# AUDIO.net
KiCad netlist of a schematic drawn in Altium Designer
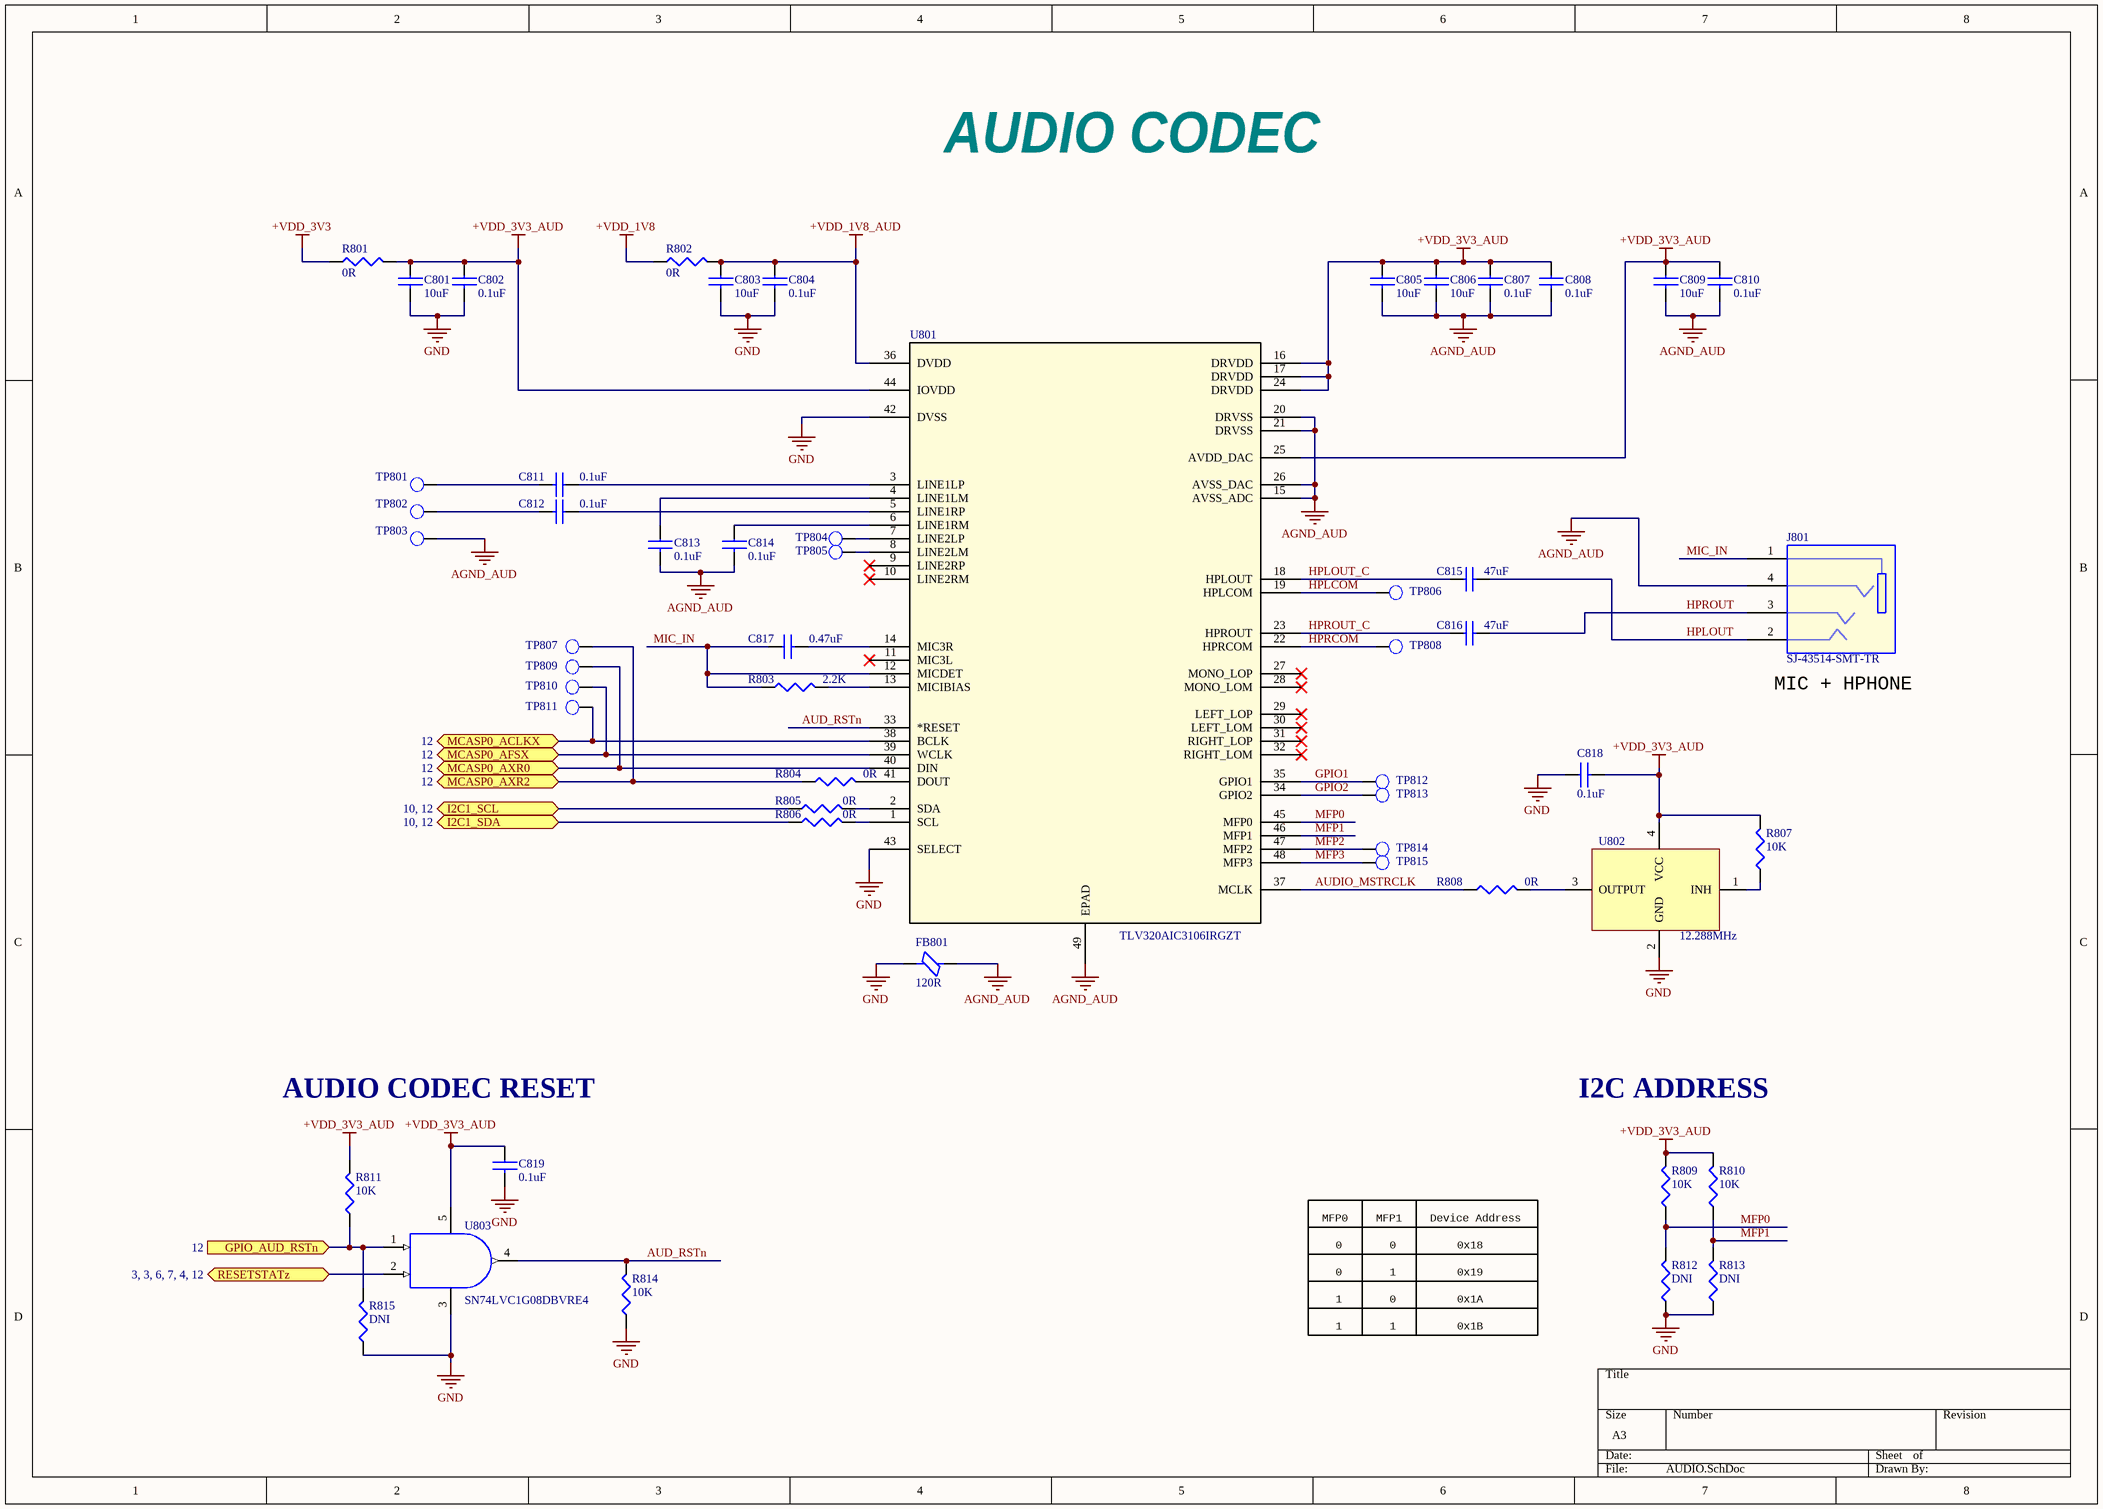
[diagram p0: AUDIO.SchDoc]

(export (version "E")
  (design (tool "Eeschema 10.0.6"))
  (components
    (comp (ref "C801")
      (value "10uF")
      (footprint "C0402")
      (description "Multilayer Ceramic Capacitor, 10 uF, 10 V, ± 20%, X5R, 0402 [1005 Metric]")
      (fields
        (field (name "MANUFACTURER") "Murata")
        (field (name "MANUFACTURER PART NUMBER") "GRM155R61A106ME11D")
      )
      (libsource (lib "Schlib SOM AM625") (part "GRM155R61A106ME11D"))
    )
    (comp (ref "C802")
      (value "0.1uF")
      (footprint "C0201")
      (description "Multilayer Ceramic Capacitor, 0.1 uF, 16 V, ± 10%, X5R, 0201 [0603 Metric]")
      (fields
        (field (name "MANUFACTURER") "Murata")
        (field (name "MANUFACTURER PART NUMBER") "GRM033R61C104KE14D")
      )
      (libsource (lib "Schlib SOM AM625") (part "GRM033R61C104KE14D"))
    )
    (comp (ref "C803")
      (value "10uF")
      (footprint "C0402")
      (description "Multilayer Ceramic Capacitor, 10 uF, 10 V, ± 20%, X5R, 0402 [1005 Metric]")
      (fields
        (field (name "MANUFACTURER") "Murata")
        (field (name "MANUFACTURER PART NUMBER") "GRM155R61A106ME11D")
      )
      (libsource (lib "Schlib SOM AM625") (part "GRM155R61A106ME11D"))
    )
    (comp (ref "C804")
      (value "0.1uF")
      (footprint "C0201")
      (description "Multilayer Ceramic Capacitor, 0.1 uF, 16 V, ± 10%, X5R, 0201 [0603 Metric]")
      (fields
        (field (name "MANUFACTURER") "Murata")
        (field (name "MANUFACTURER PART NUMBER") "GRM033R61C104KE14D")
      )
      (libsource (lib "Schlib SOM AM625") (part "GRM033R61C104KE14D"))
    )
    (comp (ref "C805")
      (value "10uF")
      (footprint "C0402")
      (description "Multilayer Ceramic Capacitor, 10 uF, 10 V, ± 20%, X5R, 0402 [1005 Metric]")
      (fields
        (field (name "MANUFACTURER") "Murata")
        (field (name "MANUFACTURER PART NUMBER") "GRM155R61A106ME11D")
      )
      (libsource (lib "Schlib SOM AM625") (part "GRM155R61A106ME11D"))
    )
    (comp (ref "C806")
      (value "10uF")
      (footprint "C0402")
      (description "Multilayer Ceramic Capacitor, 10 uF, 10 V, ± 20%, X5R, 0402 [1005 Metric]")
      (fields
        (field (name "MANUFACTURER") "Murata")
        (field (name "MANUFACTURER PART NUMBER") "GRM155R61A106ME11D")
      )
      (libsource (lib "Schlib SOM AM625") (part "GRM155R61A106ME11D"))
    )
    (comp (ref "C807")
      (value "0.1uF")
      (footprint "C0201")
      (description "Multilayer Ceramic Capacitor, 0.1 uF, 16 V, ± 10%, X5R, 0201 [0603 Metric]")
      (fields
        (field (name "MANUFACTURER") "Murata")
        (field (name "MANUFACTURER PART NUMBER") "GRM033R61C104KE14D")
      )
      (libsource (lib "Schlib SOM AM625") (part "GRM033R61C104KE14D"))
    )
    (comp (ref "C808")
      (value "0.1uF")
      (footprint "C0201")
      (description "Multilayer Ceramic Capacitor, 0.1 uF, 16 V, ± 10%, X5R, 0201 [0603 Metric]")
      (fields
        (field (name "MANUFACTURER") "Murata")
        (field (name "MANUFACTURER PART NUMBER") "GRM033R61C104KE14D")
      )
      (libsource (lib "Schlib SOM AM625") (part "GRM033R61C104KE14D"))
    )
    (comp (ref "C809")
      (value "10uF")
      (footprint "C0402")
      (description "Multilayer Ceramic Capacitor, 10 uF, 10 V, ± 20%, X5R, 0402 [1005 Metric]")
      (fields
        (field (name "MANUFACTURER") "Murata")
        (field (name "MANUFACTURER PART NUMBER") "GRM155R61A106ME11D")
      )
      (libsource (lib "Schlib SOM AM625") (part "GRM155R61A106ME11D"))
    )
    (comp (ref "C810")
      (value "0.1uF")
      (footprint "C0201")
      (description "Multilayer Ceramic Capacitor, 0.1 uF, 16 V, ± 10%, X5R, 0201 [0603 Metric]")
      (fields
        (field (name "MANUFACTURER") "Murata")
        (field (name "MANUFACTURER PART NUMBER") "GRM033R61C104KE14D")
      )
      (libsource (lib "Schlib SOM AM625") (part "GRM033R61C104KE14D"))
    )
    (comp (ref "C811")
      (value "0.1uF")
      (footprint "C0402")
      (description "Multilayer Ceramic Capacitor, 0.1 uF, 50 V, ± 10%, X7R, 0402 [1005 Metric]")
      (fields
        (field (name "MANUFACTURER") "Murata")
        (field (name "MANUFACTURER PART NUMBER") "GRM155R71H104KE14D")
      )
      (libsource (lib "Schlib SOM AM625") (part "GRM155R71H104KE14D"))
    )
    (comp (ref "C812")
      (value "0.1uF")
      (footprint "C0402")
      (description "Multilayer Ceramic Capacitor, 0.1 uF, 50 V, ± 10%, X7R, 0402 [1005 Metric]")
      (fields
        (field (name "MANUFACTURER") "Murata")
        (field (name "MANUFACTURER PART NUMBER") "GRM155R71H104KE14D")
      )
      (libsource (lib "Schlib SOM AM625") (part "GRM155R71H104KE14D"))
    )
    (comp (ref "C813")
      (value "0.1uF")
      (footprint "C0201")
      (description "Multilayer Ceramic Capacitor, 0.1 uF, 16 V, ± 10%, X5R, 0201 [0603 Metric]")
      (fields
        (field (name "MANUFACTURER") "Murata")
        (field (name "MANUFACTURER PART NUMBER") "GRM033R61C104KE14D")
      )
      (libsource (lib "Schlib SOM AM625") (part "GRM033R61C104KE14D"))
    )
    (comp (ref "C814")
      (value "0.1uF")
      (footprint "C0201")
      (description "Multilayer Ceramic Capacitor, 0.1 uF, 16 V, ± 10%, X5R, 0201 [0603 Metric]")
      (fields
        (field (name "MANUFACTURER") "Murata")
        (field (name "MANUFACTURER PART NUMBER") "GRM033R61C104KE14D")
      )
      (libsource (lib "Schlib SOM AM625") (part "GRM033R61C104KE14D"))
    )
    (comp (ref "C815")
      (value "47uF")
      (footprint "C1206B/3216MM")
      (description "Multilayer Ceramic Capacitor, 47 uF, 10 V, ± 20%, X5R, 1206 [3216 Metric]")
      (fields
        (field (name "MANUFACTURER") "Murata")
        (field (name "MANUFACTURER PART NUMBER") "GRM31CR61A476ME15L")
      )
      (libsource (lib "Schlib SOM AM625") (part "GRM31CR61A476ME15L"))
    )
    (comp (ref "C816")
      (value "47uF")
      (footprint "C1206B/3216MM")
      (description "Multilayer Ceramic Capacitor, 47 uF, 10 V, ± 20%, X5R, 1206 [3216 Metric]")
      (fields
        (field (name "MANUFACTURER") "Murata")
        (field (name "MANUFACTURER PART NUMBER") "GRM31CR61A476ME15L")
      )
      (libsource (lib "Schlib SOM AM625") (part "GRM31CR61A476ME15L"))
    )
    (comp (ref "C817")
      (value "0.47uF")
      (footprint "C0402")
      (description "Multilayer Ceramic Capacitor, 0.47 uF, 10 V, ± 10%, X7R, 0402 [1005 Metric]")
      (fields
        (field (name "MANUFACTURER") "Murata")
        (field (name "MANUFACTURER PART NUMBER") "GRM155R71A474KE01D")
      )
      (libsource (lib "Schlib SOM AM625") (part "GRM155R71A474KE01D"))
    )
    (comp (ref "C818")
      (value "0.1uF")
      (footprint "C0201")
      (description "Multilayer Ceramic Capacitor, 0.1 uF, 16 V, ± 10%, X5R, 0201 [0603 Metric]")
      (fields
        (field (name "MANUFACTURER") "Murata")
        (field (name "MANUFACTURER PART NUMBER") "GRM033R61C104KE14D")
      )
      (libsource (lib "Schlib SOM AM625") (part "GRM033R61C104KE14D"))
    )
    (comp (ref "C819")
      (value "0.1uF")
      (footprint "C0402")
      (description "Multilayer Ceramic Capacitor, 0.1 uF, 50 V, ± 10%, X7R, 0402 [1005 Metric]")
      (fields
        (field (name "MANUFACTURER") "Murata")
        (field (name "MANUFACTURER PART NUMBER") "GRM155R71H104KE14D")
      )
      (libsource (lib "Schlib SOM AM625") (part "GRM155R71H104KE14D"))
    )
    (comp (ref "FB801")
      (value "120R")
      (footprint "FB0402")
      (description "Ferrite Beads Multi-Layer 120Ohm 25% 100MHz 1.3A 0.09Ohm DCR 0402 Automotive T/R")
      (fields
        (field (name "MANUFACTURER") "Murata")
        (field (name "MANUFACTURER PART NUMBER") "BLM15PD121SZ1D")
      )
      (libsource (lib "Schlib SOM AM625") (part "BLM15PD121SZ1D"))
    )
    (comp (ref "J801")
      (value "SJ-43514-SMT-TR")
      (footprint "CON_AV4_SJ-43514-SMT_S_R_S_5-1")
      (description "3.5 mm, 4 Conductors, Right Angle, Surface Mount (SMT), Audio Jack Connector")
      (fields (field (name "MANUFACTURER") "CUI Devices"))
      (libsource (lib "Schlib SOM AM625") (part "SJ-43514-SMT-TR"))
    )
    (comp (ref "R801")
      (value "0R")
      (footprint "R0201")
      (description "Zero Ohm Resistor, Jumper, 0201 [0603 Metric], Thick Film, 50 mW, 500 mA, Surface Mount")
      (fields
        (field (name "MANUFACTURER") "Yageo")
        (field (name "MANUFACTURER PART NUMBER") "RC0201JR-070RL")
      )
      (libsource (lib "Schlib SOM AM625") (part "RC0201JR-070RL"))
    )
    (comp (ref "R802")
      (value "0R")
      (footprint "R0201")
      (description "Zero Ohm Resistor, Jumper, 0201 [0603 Metric], Thick Film, 50 mW, 500 mA, Surface Mount")
      (fields
        (field (name "MANUFACTURER") "Yageo")
        (field (name "MANUFACTURER PART NUMBER") "RC0201JR-070RL")
      )
      (libsource (lib "Schlib SOM AM625") (part "RC0201JR-070RL"))
    )
    (comp (ref "R803")
      (value "2.2K")
      (footprint "R0201")
      (description "SMD Chip Resistor, 2.2 kOhm, ± 1%, 50 mW, 0201 [0603 Metric], Thick Film, General Purpose")
      (fields
        (field (name "MANUFACTURER") "Yageo")
        (field (name "MANUFACTURER PART NUMBER") "RC0201FR-072K2L")
      )
      (libsource (lib "Schlib SOM AM625") (part "RC0201FR-072K2L"))
    )
    (comp (ref "R804")
      (value "0R")
      (footprint "R0201")
      (description "Zero Ohm Resistor, Jumper, 0201 [0603 Metric], Thick Film, 50 mW, 500 mA, Surface Mount")
      (fields
        (field (name "MANUFACTURER") "Yageo")
        (field (name "MANUFACTURER PART NUMBER") "RC0201JR-070RL")
      )
      (libsource (lib "Schlib SOM AM625") (part "RC0201JR-070RL"))
    )
    (comp (ref "R805")
      (value "0R")
      (footprint "R0402")
      (description "Zero Ohm Resistor, Jumper, 0402 [1005 Metric], Thick Film, 63 mW, 1 A, Surface Mount")
      (fields
        (field (name "MANUFACTURER") "Yageo")
        (field (name "MANUFACTURER PART NUMBER") "RC0402JR-070RL")
      )
      (libsource (lib "Schlib SOM AM625") (part "RC0402JR-070RL"))
    )
    (comp (ref "R806")
      (value "0R")
      (footprint "R0402")
      (description "Zero Ohm Resistor, Jumper, 0402 [1005 Metric], Thick Film, 63 mW, 1 A, Surface Mount")
      (fields
        (field (name "MANUFACTURER") "Yageo")
        (field (name "MANUFACTURER PART NUMBER") "RC0402JR-070RL")
      )
      (libsource (lib "Schlib SOM AM625") (part "RC0402JR-070RL"))
    )
    (comp (ref "R807")
      (value "10K")
      (footprint "R0201")
      (description "Res Thick Film 0201 10K Ohm 5% 1/20W ±200ppm/°C Molded SMD SMD Paper T/R")
      (fields
        (field (name "MANUFACTURER") "Yageo")
        (field (name "MANUFACTURER PART NUMBER") "RC0201JR-0710KL")
      )
      (libsource (lib "Schlib SOM AM625") (part "RC0201JR-0710KL"))
    )
    (comp (ref "R808")
      (value "0R")
      (footprint "R0201")
      (description "Zero Ohm Resistor, Jumper, 0201 [0603 Metric], Thick Film, 50 mW, 500 mA, Surface Mount")
      (fields
        (field (name "MANUFACTURER") "Yageo")
        (field (name "MANUFACTURER PART NUMBER") "RC0201JR-070RL")
      )
      (libsource (lib "Schlib SOM AM625") (part "RC0201JR-070RL"))
    )
    (comp (ref "R809")
      (value "10K")
      (footprint "R0201")
      (description "Res Thick Film 0201 10K Ohm 5% 1/20W ±200ppm/°C Molded SMD SMD Paper T/R")
      (fields
        (field (name "MANUFACTURER") "Yageo")
        (field (name "MANUFACTURER PART NUMBER") "RC0201JR-0710KL")
      )
      (libsource (lib "Schlib SOM AM625") (part "RC0201JR-0710KL"))
    )
    (comp (ref "R810")
      (value "10K")
      (footprint "R0201")
      (description "Res Thick Film 0201 10K Ohm 5% 1/20W ±200ppm/°C Molded SMD SMD Paper T/R")
      (fields
        (field (name "MANUFACTURER") "Yageo")
        (field (name "MANUFACTURER PART NUMBER") "RC0201JR-0710KL")
      )
      (libsource (lib "Schlib SOM AM625") (part "RC0201JR-0710KL"))
    )
    (comp (ref "R811")
      (value "10K")
      (footprint "R0201")
      (description "Res Thick Film 0201 10K Ohm 5% 1/20W ±200ppm/°C Molded SMD SMD Paper T/R")
      (fields
        (field (name "MANUFACTURER") "Yageo")
        (field (name "MANUFACTURER PART NUMBER") "RC0201JR-0710KL")
      )
      (libsource (lib "Schlib SOM AM625") (part "RC0201JR-0710KL"))
    )
    (comp (ref "R812")
      (value "DNI")
      (footprint "R0201")
      (description "Res Thick Film 0201 10K Ohm 5% 1/20W ±200ppm/°C Molded SMD SMD Paper T/R")
      (fields
        (field (name "MANUFACTURER") "Yageo")
        (field (name "MANUFACTURER PART NUMBER") "RC0201JR-0710KL")
      )
      (libsource (lib "Schlib SOM AM625") (part "RC0201JR-0710KL"))
    )
    (comp (ref "R813")
      (value "DNI")
      (footprint "R0201")
      (description "Res Thick Film 0201 10K Ohm 5% 1/20W ±200ppm/°C Molded SMD SMD Paper T/R")
      (fields
        (field (name "MANUFACTURER") "Yageo")
        (field (name "MANUFACTURER PART NUMBER") "RC0201JR-0710KL")
      )
      (libsource (lib "Schlib SOM AM625") (part "RC0201JR-0710KL"))
    )
    (comp (ref "R814")
      (value "10K")
      (footprint "R0201")
      (description "Res Thick Film 0201 10K Ohm 5% 1/20W ±200ppm/°C Molded SMD SMD Paper T/R")
      (fields
        (field (name "MANUFACTURER") "Yageo")
        (field (name "MANUFACTURER PART NUMBER") "RC0201JR-0710KL")
      )
      (libsource (lib "Schlib SOM AM625") (part "RC0201JR-0710KL"))
    )
    (comp (ref "R815")
      (value "DNI")
      (footprint "R0201")
      (description "Res Thick Film 0201 10K Ohm 5% 1/20W ±200ppm/°C Molded SMD SMD Paper T/R")
      (fields
        (field (name "MANUFACTURER") "Yageo")
        (field (name "MANUFACTURER PART NUMBER") "RC0201JR-0710KL")
      )
      (libsource (lib "Schlib SOM AM625") (part "RC0201JR-0710KL"))
    )
    (comp (ref "TP801")
      (value "THRU HOLE")
      (footprint "TP_40X65")
      (description "TESTPOINT 1.0MM DRILL PTH")
      (fields (field (name "DISTRIBUTOR_PART_NUMBER") "NA") (field (name "MFR_PART_NUMBER") "TP_40X65"))
      (libsource (lib "Schlib SOM AM625") (part "TESTPOINT"))
    )
    (comp (ref "TP802")
      (value "THRU HOLE")
      (footprint "TP_40X65")
      (description "TESTPOINT 1.0MM DRILL PTH")
      (fields (field (name "DISTRIBUTOR_PART_NUMBER") "NA") (field (name "MFR_PART_NUMBER") "TP_40X65"))
      (libsource (lib "Schlib SOM AM625") (part "TESTPOINT"))
    )
    (comp (ref "TP803")
      (value "THRU HOLE")
      (footprint "TP_40X65")
      (description "TESTPOINT 1.0MM DRILL PTH")
      (fields (field (name "DISTRIBUTOR_PART_NUMBER") "NA") (field (name "MFR_PART_NUMBER") "TP_40X65"))
      (libsource (lib "Schlib SOM AM625") (part "TESTPOINT"))
    )
    (comp (ref "TP804")
      (value "TP20_SMD")
      (footprint "TP20_SMD")
      (description "TESTPOINT CIR 20 SMD")
      (fields
        (field (name "MISTRAL PART NO") "NA")
        (field (name "LIBRARY PATH") "Y~{:}MIS_DATABAS~{E}Librar~{y}ALTIUM_TOO~{L}SCHEMATICS_PART~{S}MS_DISCRETE_Library.schlib")
      )
      (libsource (lib "Schlib SOM AM625") (part "TESTPOINT_1"))
    )
    (comp (ref "TP805")
      (value "TP20_SMD")
      (footprint "TP20_SMD")
      (description "TESTPOINT CIR 20 SMD")
      (fields
        (field (name "MISTRAL PART NO") "NA")
        (field (name "LIBRARY PATH") "Y~{:}MIS_DATABAS~{E}Librar~{y}ALTIUM_TOO~{L}SCHEMATICS_PART~{S}MS_DISCRETE_Library.schlib")
      )
      (libsource (lib "Schlib SOM AM625") (part "TESTPOINT_1"))
    )
    (comp (ref "TP806")
      (value "TP20_SMD")
      (footprint "TP20_SMD")
      (description "TESTPOINT CIR 20 SMD")
      (fields
        (field (name "MISTRAL PART NO") "NA")
        (field (name "LIBRARY PATH") "Y~{:}MIS_DATABAS~{E}Librar~{y}ALTIUM_TOO~{L}SCHEMATICS_PART~{S}MS_DISCRETE_Library.schlib")
      )
      (libsource (lib "Schlib SOM AM625") (part "TESTPOINT_1"))
    )
    (comp (ref "TP807")
      (value "TP20_SMD")
      (footprint "TP20_SMD")
      (description "TESTPOINT CIR 20 SMD")
      (fields
        (field (name "MISTRAL PART NO") "NA")
        (field (name "LIBRARY PATH") "Y~{:}MIS_DATABAS~{E}Librar~{y}ALTIUM_TOO~{L}SCHEMATICS_PART~{S}MS_DISCRETE_Library.schlib")
      )
      (libsource (lib "Schlib SOM AM625") (part "TESTPOINT_1"))
    )
    (comp (ref "TP808")
      (value "TP20_SMD")
      (footprint "TP20_SMD")
      (description "TESTPOINT CIR 20 SMD")
      (fields
        (field (name "MISTRAL PART NO") "NA")
        (field (name "LIBRARY PATH") "Y~{:}MIS_DATABAS~{E}Librar~{y}ALTIUM_TOO~{L}SCHEMATICS_PART~{S}MS_DISCRETE_Library.schlib")
      )
      (libsource (lib "Schlib SOM AM625") (part "TESTPOINT_1"))
    )
    (comp (ref "TP809")
      (value "TP20_SMD")
      (footprint "TP20_SMD")
      (description "TESTPOINT CIR 20 SMD")
      (fields
        (field (name "MISTRAL PART NO") "NA")
        (field (name "LIBRARY PATH") "Y~{:}MIS_DATABAS~{E}Librar~{y}ALTIUM_TOO~{L}SCHEMATICS_PART~{S}MS_DISCRETE_Library.schlib")
      )
      (libsource (lib "Schlib SOM AM625") (part "TESTPOINT_1"))
    )
    (comp (ref "TP810")
      (value "TP20_SMD")
      (footprint "TP20_SMD")
      (description "TESTPOINT CIR 20 SMD")
      (fields
        (field (name "MISTRAL PART NO") "NA")
        (field (name "LIBRARY PATH") "Y~{:}MIS_DATABAS~{E}Librar~{y}ALTIUM_TOO~{L}SCHEMATICS_PART~{S}MS_DISCRETE_Library.schlib")
      )
      (libsource (lib "Schlib SOM AM625") (part "TESTPOINT_1"))
    )
    (comp (ref "TP811")
      (value "TP20_SMD")
      (footprint "TP20_SMD")
      (description "TESTPOINT CIR 20 SMD")
      (fields
        (field (name "MISTRAL PART NO") "NA")
        (field (name "LIBRARY PATH") "Y~{:}MIS_DATABAS~{E}Librar~{y}ALTIUM_TOO~{L}SCHEMATICS_PART~{S}MS_DISCRETE_Library.schlib")
      )
      (libsource (lib "Schlib SOM AM625") (part "TESTPOINT_1"))
    )
    (comp (ref "TP812")
      (value "TP20_SMD")
      (footprint "TP20_SMD")
      (description "TESTPOINT CIR 20 SMD")
      (fields
        (field (name "MISTRAL PART NO") "NA")
        (field (name "LIBRARY PATH") "Y~{:}MIS_DATABAS~{E}Librar~{y}ALTIUM_TOO~{L}SCHEMATICS_PART~{S}MS_DISCRETE_Library.schlib")
      )
      (libsource (lib "Schlib SOM AM625") (part "TESTPOINT_1"))
    )
    (comp (ref "TP813")
      (value "TP20_SMD")
      (footprint "TP20_SMD")
      (description "TESTPOINT CIR 20 SMD")
      (fields
        (field (name "MISTRAL PART NO") "NA")
        (field (name "LIBRARY PATH") "Y~{:}MIS_DATABAS~{E}Librar~{y}ALTIUM_TOO~{L}SCHEMATICS_PART~{S}MS_DISCRETE_Library.schlib")
      )
      (libsource (lib "Schlib SOM AM625") (part "TESTPOINT_1"))
    )
    (comp (ref "TP814")
      (value "TP20_SMD")
      (footprint "TP20_SMD")
      (description "TESTPOINT CIR 20 SMD")
      (fields
        (field (name "MISTRAL PART NO") "NA")
        (field (name "LIBRARY PATH") "Y~{:}MIS_DATABAS~{E}Librar~{y}ALTIUM_TOO~{L}SCHEMATICS_PART~{S}MS_DISCRETE_Library.schlib")
      )
      (libsource (lib "Schlib SOM AM625") (part "TESTPOINT_1"))
    )
    (comp (ref "TP815")
      (value "TP20_SMD")
      (footprint "TP20_SMD")
      (description "TESTPOINT CIR 20 SMD")
      (fields
        (field (name "MISTRAL PART NO") "NA")
        (field (name "LIBRARY PATH") "Y~{:}MIS_DATABAS~{E}Librar~{y}ALTIUM_TOO~{L}SCHEMATICS_PART~{S}MS_DISCRETE_Library.schlib")
      )
      (libsource (lib "Schlib SOM AM625") (part "TESTPOINT_1"))
    )
    (comp (ref "U801")
      (value "TLV320AIC3106IRGZT")
      (footprint "VQFN48_19-68_285X285")
      (description "Very-Low-Power Stereo Audio CODEC With PowerTune Technology 32-VQFN -40 to 85")
      (fields
        (field (name "MANUFACTURER") "Texas Instruments")
        (field (name "MANUFACTURER PART NUMBER") "TLV320AIC3204IRHBR")
      )
      (libsource (lib "Schlib SOM AM625") (part "TLV320AIC3204IRHBR"))
    )
    (comp (ref "U802")
      (value "12.288MHz")
      (footprint "OSC4_KC2520B_100X80_SMD_0-8")
      (description "12.288 MHz XO (Standard) CMOS Oscillator 1.71V ~ 3.63V Standby (Power Down) 4-SMD, No Lead")
      (fields
        (field (name "MANUFACTURER") "Kyocera AVX")
        (field (name "MANUFACTURER PART NUMBER") "KC2520Z12.2880C1KX00")
      )
      (libsource (lib "Schlib SOM AM625") (part "XTAL OSC XO 12.2880MHZ CMOS SMD"))
    )
    (comp (ref "U803")
      (value "SN74LVC1G08DBVRE4")
      (footprint "SOT23-5")
      (description "Single 2-input, 1.65-V to 5.5-V AND gate 5-SOT-23 -40 to 125")
      (fields (field (name "MANUFACTURER") "Texas Instruments"))
      (libsource (lib "Schlib SOM AM625") (part "SN74LVC1G08DBVRE4"))
    )
  )
  (nets
    (net (code "1") (name "+VDD_1V8") (class "Default")
      (node (ref "R802") (pin "1") (pinfunction "1_1") (pintype "passive"))
    )
    (net (code "2") (name "+VDD_1V8_AUD") (class "Default")
      (node (ref "C803") (pin "1") (pinfunction "1_1") (pintype "passive"))
      (node (ref "C804") (pin "1") (pinfunction "1_1") (pintype "passive"))
      (node (ref "R802") (pin "2") (pinfunction "2_2") (pintype "passive"))
      (node (ref "U801") (pin "36") (pinfunction "DVDD_36") (pintype "passive"))
    )
    (net (code "3") (name "+VDD_3V3") (class "Default")
      (node (ref "R801") (pin "1") (pinfunction "1_1") (pintype "passive"))
    )
    (net (code "4") (name "+VDD_3V3_AUD") (class "Default")
      (node (ref "C801") (pin "1") (pinfunction "1_1") (pintype "passive"))
      (node (ref "C802") (pin "1") (pinfunction "1_1") (pintype "passive"))
      (node (ref "C805") (pin "1") (pinfunction "1_1") (pintype "passive"))
      (node (ref "C806") (pin "1") (pinfunction "1_1") (pintype "passive"))
      (node (ref "C807") (pin "1") (pinfunction "1_1") (pintype "passive"))
      (node (ref "C808") (pin "1") (pinfunction "1_1") (pintype "passive"))
      (node (ref "C809") (pin "1") (pinfunction "1_1") (pintype "passive"))
      (node (ref "C810") (pin "1") (pinfunction "1_1") (pintype "passive"))
      (node (ref "C818") (pin "2") (pinfunction "2_2") (pintype "passive"))
      (node (ref "C819") (pin "1") (pinfunction "1_1") (pintype "passive"))
      (node (ref "R801") (pin "2") (pinfunction "2_2") (pintype "passive"))
      (node (ref "R807") (pin "2") (pinfunction "2_2") (pintype "passive"))
      (node (ref "R809") (pin "2") (pinfunction "2_2") (pintype "passive"))
      (node (ref "R810") (pin "2") (pinfunction "2_2") (pintype "passive"))
      (node (ref "R811") (pin "2") (pinfunction "2_2") (pintype "passive"))
      (node (ref "U801") (pin "16") (pinfunction "DRVDD_16") (pintype "passive"))
      (node (ref "U801") (pin "17") (pinfunction "DRVDD_17") (pintype "passive"))
      (node (ref "U801") (pin "24") (pinfunction "DRVDD_24") (pintype "passive"))
      (node (ref "U801") (pin "25") (pinfunction "AVDD_DAC_25") (pintype "passive"))
      (node (ref "U801") (pin "44") (pinfunction "IOVDD_44") (pintype "passive"))
      (node (ref "U802") (pin "4") (pinfunction "VCC_4") (pintype "passive"))
      (node (ref "U803") (pin "5") (pinfunction "V+_5") (pintype "power_in"))
    )
    (net (code "5") (name "/AUDIO_MSTRCLK") (class "Default")
      (node (ref "R808") (pin "1") (pinfunction "1_1") (pintype "passive"))
      (node (ref "U801") (pin "37") (pinfunction "MCLK_37") (pintype "passive"))
    )
    (net (code "6") (name "/AUD_RSTn") (class "Default")
      (node (ref "R814") (pin "2") (pinfunction "2_2") (pintype "passive"))
      (node (ref "U801") (pin "33") (pinfunction "*RESET_33") (pintype "passive"))
      (node (ref "U803") (pin "4") (pinfunction "Y_4") (pintype "output"))
    )
    (net (code "7") (name "/GPIO1") (class "Default")
      (node (ref "TP812") (pin "1") (pinfunction "TP_1") (pintype "passive"))
      (node (ref "U801") (pin "35") (pinfunction "GPIO1_35") (pintype "passive"))
    )
    (net (code "8") (name "/GPIO2") (class "Default")
      (node (ref "TP813") (pin "1") (pinfunction "TP_1") (pintype "passive"))
      (node (ref "U801") (pin "34") (pinfunction "GPIO2_34") (pintype "passive"))
    )
    (net (code "9") (name "/GPIO_AUD_RSTn") (class "Default")
      (node (ref "R811") (pin "1") (pinfunction "1_1") (pintype "passive"))
      (node (ref "R815") (pin "2") (pinfunction "2_2") (pintype "passive"))
      (node (ref "U803") (pin "1") (pinfunction "A_1") (pintype "input"))
    )
    (net (code "10") (name "/HPLCOM") (class "Default")
      (node (ref "TP806") (pin "1") (pinfunction "TP_1") (pintype "passive"))
      (node (ref "U801") (pin "19") (pinfunction "HPLCOM_19") (pintype "passive"))
    )
    (net (code "11") (name "/HPLOUT") (class "Default")
      (node (ref "C815") (pin "2") (pinfunction "2_2") (pintype "passive"))
      (node (ref "J801") (pin "2") (pinfunction "2_2") (pintype "passive"))
    )
    (net (code "12") (name "/HPLOUT_C") (class "Default")
      (node (ref "C815") (pin "1") (pinfunction "1_1") (pintype "passive"))
      (node (ref "U801") (pin "18") (pinfunction "HPLOUT_18") (pintype "passive"))
    )
    (net (code "13") (name "/HPRCOM") (class "Default")
      (node (ref "TP808") (pin "1") (pinfunction "TP_1") (pintype "passive"))
      (node (ref "U801") (pin "22") (pinfunction "HPRCOM_22") (pintype "passive"))
    )
    (net (code "14") (name "/HPROUT") (class "Default")
      (node (ref "C816") (pin "2") (pinfunction "2_2") (pintype "passive"))
      (node (ref "J801") (pin "3") (pinfunction "3_3") (pintype "passive"))
    )
    (net (code "15") (name "/HPROUT_C") (class "Default")
      (node (ref "C816") (pin "1") (pinfunction "1_1") (pintype "passive"))
      (node (ref "U801") (pin "23") (pinfunction "HPROUT_23") (pintype "passive"))
    )
    (net (code "16") (name "/I2C1_SCL") (class "Default")
      (node (ref "R805") (pin "1") (pinfunction "1_1") (pintype "passive"))
    )
    (net (code "17") (name "/I2C1_SDA") (class "Default")
      (node (ref "R806") (pin "1") (pinfunction "1_1") (pintype "passive"))
    )
    (net (code "18") (name "/MCASP0_ACLKX") (class "Default")
      (node (ref "TP811") (pin "1") (pinfunction "TP_1") (pintype "passive"))
      (node (ref "U801") (pin "38") (pinfunction "BCLK_38") (pintype "passive"))
    )
    (net (code "19") (name "/MCASP0_AFSX") (class "Default")
      (node (ref "TP810") (pin "1") (pinfunction "TP_1") (pintype "passive"))
      (node (ref "U801") (pin "39") (pinfunction "WCLK_39") (pintype "passive"))
    )
    (net (code "20") (name "/MCASP0_AXR0") (class "Default")
      (node (ref "TP809") (pin "1") (pinfunction "TP_1") (pintype "passive"))
      (node (ref "U801") (pin "40") (pinfunction "DIN_40") (pintype "passive"))
    )
    (net (code "21") (name "/MCASP0_AXR2") (class "Default")
      (node (ref "R804") (pin "1") (pinfunction "1_1") (pintype "passive"))
      (node (ref "TP807") (pin "1") (pinfunction "TP_1") (pintype "passive"))
    )
    (net (code "22") (name "/MFP0") (class "Default")
      (node (ref "R809") (pin "1") (pinfunction "1_1") (pintype "passive"))
      (node (ref "R812") (pin "2") (pinfunction "2_2") (pintype "passive"))
      (node (ref "U801") (pin "45") (pinfunction "MFP0_45") (pintype "passive"))
    )
    (net (code "23") (name "/MFP1") (class "Default")
      (node (ref "R810") (pin "1") (pinfunction "1_1") (pintype "passive"))
      (node (ref "R813") (pin "2") (pinfunction "2_2") (pintype "passive"))
      (node (ref "U801") (pin "46") (pinfunction "MFP1_46") (pintype "passive"))
    )
    (net (code "24") (name "/MFP2") (class "Default")
      (node (ref "TP814") (pin "1") (pinfunction "TP_1") (pintype "passive"))
      (node (ref "U801") (pin "47") (pinfunction "MFP2_47") (pintype "passive"))
    )
    (net (code "25") (name "/MFP3") (class "Default")
      (node (ref "TP815") (pin "1") (pinfunction "TP_1") (pintype "passive"))
      (node (ref "U801") (pin "48") (pinfunction "MFP3_48") (pintype "passive"))
    )
    (net (code "26") (name "/MIC_IN") (class "Default")
      (node (ref "C817") (pin "1") (pinfunction "1_1") (pintype "passive"))
      (node (ref "J801") (pin "1") (pinfunction "1_1") (pintype "passive"))
      (node (ref "R803") (pin "1") (pinfunction "1_1") (pintype "passive"))
      (node (ref "U801") (pin "12") (pinfunction "MICDET_12") (pintype "passive"))
    )
    (net (code "27") (name "/RESETSTATz") (class "Default")
      (node (ref "U803") (pin "2") (pinfunction "B_2") (pintype "input"))
    )
    (net (code "28") (name "AGND_AUD") (class "Default")
      (node (ref "C805") (pin "2") (pinfunction "2_2") (pintype "passive"))
      (node (ref "C806") (pin "2") (pinfunction "2_2") (pintype "passive"))
      (node (ref "C807") (pin "2") (pinfunction "2_2") (pintype "passive"))
      (node (ref "C808") (pin "2") (pinfunction "2_2") (pintype "passive"))
      (node (ref "C809") (pin "2") (pinfunction "2_2") (pintype "passive"))
      (node (ref "C810") (pin "2") (pinfunction "2_2") (pintype "passive"))
      (node (ref "C813") (pin "2") (pinfunction "2_2") (pintype "passive"))
      (node (ref "C814") (pin "2") (pinfunction "2_2") (pintype "passive"))
      (node (ref "FB801") (pin "1") (pinfunction "1_1") (pintype "passive"))
      (node (ref "J801") (pin "4") (pinfunction "4_4") (pintype "passive"))
      (node (ref "TP803") (pin "1") (pinfunction "TP_1") (pintype "passive"))
      (node (ref "U801") (pin "15") (pinfunction "AVSS_ADC_15") (pintype "passive"))
      (node (ref "U801") (pin "20") (pinfunction "DRVSS_20") (pintype "passive"))
      (node (ref "U801") (pin "21") (pinfunction "DRVSS_21") (pintype "passive"))
      (node (ref "U801") (pin "26") (pinfunction "AVSS_DAC_26") (pintype "passive"))
      (node (ref "U801") (pin "49") (pinfunction "EPAD_49") (pintype "passive"))
    )
    (net (code "29") (name "GND") (class "Default")
      (node (ref "C801") (pin "2") (pinfunction "2_2") (pintype "passive"))
      (node (ref "C802") (pin "2") (pinfunction "2_2") (pintype "passive"))
      (node (ref "C803") (pin "2") (pinfunction "2_2") (pintype "passive"))
      (node (ref "C804") (pin "2") (pinfunction "2_2") (pintype "passive"))
      (node (ref "C818") (pin "1") (pinfunction "1_1") (pintype "passive"))
      (node (ref "C819") (pin "2") (pinfunction "2_2") (pintype "passive"))
      (node (ref "FB801") (pin "2") (pinfunction "2_2") (pintype "passive"))
      (node (ref "R812") (pin "1") (pinfunction "1_1") (pintype "passive"))
      (node (ref "R813") (pin "1") (pinfunction "1_1") (pintype "passive"))
      (node (ref "R814") (pin "1") (pinfunction "1_1") (pintype "passive"))
      (node (ref "R815") (pin "1") (pinfunction "1_1") (pintype "passive"))
      (node (ref "U801") (pin "42") (pinfunction "DVSS_42") (pintype "passive"))
      (node (ref "U801") (pin "43") (pinfunction "SELECT_43") (pintype "passive"))
      (node (ref "U802") (pin "2") (pinfunction "GND_2") (pintype "passive"))
      (node (ref "U803") (pin "3") (pinfunction "V-_3") (pintype "power_in"))
    )
    (net (code "30") (name "Net-(TP801-TP)") (class "Default")
      (node (ref "C811") (pin "2") (pinfunction "2_2") (pintype "passive"))
      (node (ref "TP801") (pin "1") (pinfunction "TP_1") (pintype "passive"))
    )
    (net (code "31") (name "Net-(TP802-TP)") (class "Default")
      (node (ref "C812") (pin "2") (pinfunction "2_2") (pintype "passive"))
      (node (ref "TP802") (pin "1") (pinfunction "TP_1") (pintype "passive"))
    )
    (net (code "32") (name "Net-(TP804-TP)") (class "Default")
      (node (ref "TP804") (pin "1") (pinfunction "TP_1") (pintype "passive"))
      (node (ref "U801") (pin "7") (pinfunction "LINE2LP_7") (pintype "passive"))
    )
    (net (code "33") (name "Net-(TP805-TP)") (class "Default")
      (node (ref "TP805") (pin "1") (pinfunction "TP_1") (pintype "passive"))
      (node (ref "U801") (pin "8") (pinfunction "LINE2LM_8") (pintype "passive"))
    )
    (net (code "34") (name "Net-(U801-DOUT)") (class "Default")
      (node (ref "R804") (pin "2") (pinfunction "2_2") (pintype "passive"))
      (node (ref "U801") (pin "41") (pinfunction "DOUT_41") (pintype "passive"))
    )
    (net (code "35") (name "Net-(U801-LINE1LM)") (class "Default")
      (node (ref "C813") (pin "1") (pinfunction "1_1") (pintype "passive"))
      (node (ref "U801") (pin "4") (pinfunction "LINE1LM_4") (pintype "passive"))
    )
    (net (code "36") (name "Net-(U801-LINE1LP)") (class "Default")
      (node (ref "C811") (pin "1") (pinfunction "1_1") (pintype "passive"))
      (node (ref "U801") (pin "3") (pinfunction "LINE1LP_3") (pintype "passive"))
    )
    (net (code "37") (name "Net-(U801-LINE1RM)") (class "Default")
      (node (ref "C814") (pin "1") (pinfunction "1_1") (pintype "passive"))
      (node (ref "U801") (pin "6") (pinfunction "LINE1RM_6") (pintype "passive"))
    )
    (net (code "38") (name "Net-(U801-LINE1RP)") (class "Default")
      (node (ref "C812") (pin "1") (pinfunction "1_1") (pintype "passive"))
      (node (ref "U801") (pin "5") (pinfunction "LINE1RP_5") (pintype "passive"))
    )
    (net (code "39") (name "Net-(U801-MIC3R)") (class "Default")
      (node (ref "C817") (pin "2") (pinfunction "2_2") (pintype "passive"))
      (node (ref "U801") (pin "14") (pinfunction "MIC3R_14") (pintype "passive"))
    )
    (net (code "40") (name "Net-(U801-MICIBIAS)") (class "Default")
      (node (ref "R803") (pin "2") (pinfunction "2_2") (pintype "passive"))
      (node (ref "U801") (pin "13") (pinfunction "MICIBIAS_13") (pintype "passive"))
    )
    (net (code "41") (name "Net-(U801-SCL)") (class "Default")
      (node (ref "R806") (pin "2") (pinfunction "2_2") (pintype "passive"))
      (node (ref "U801") (pin "1") (pinfunction "SCL_1") (pintype "passive"))
    )
    (net (code "42") (name "Net-(U801-SDA)") (class "Default")
      (node (ref "R805") (pin "2") (pinfunction "2_2") (pintype "passive"))
      (node (ref "U801") (pin "2") (pinfunction "SDA_2") (pintype "passive"))
    )
    (net (code "43") (name "Net-(U802-INH)") (class "Default")
      (node (ref "R807") (pin "1") (pinfunction "1_1") (pintype "passive"))
      (node (ref "U802") (pin "1") (pinfunction "INH_1") (pintype "passive"))
    )
    (net (code "44") (name "Net-(U802-OUTPUT)") (class "Default")
      (node (ref "R808") (pin "2") (pinfunction "2_2") (pintype "passive"))
      (node (ref "U802") (pin "3") (pinfunction "OUTPUT_3") (pintype "passive"))
    )
    (net (code "45") (name "unconnected-(U801-LEFT_LOM-Pad30)") (class "Default")
      (node (ref "U801") (pin "30") (pinfunction "LEFT_LOM_30") (pintype "passive+no_connect"))
    )
    (net (code "46") (name "unconnected-(U801-LEFT_LOP-Pad29)") (class "Default")
      (node (ref "U801") (pin "29") (pinfunction "LEFT_LOP_29") (pintype "passive+no_connect"))
    )
    (net (code "47") (name "unconnected-(U801-LINE2RM-Pad10)") (class "Default")
      (node (ref "U801") (pin "10") (pinfunction "LINE2RM_10") (pintype "passive+no_connect"))
    )
    (net (code "48") (name "unconnected-(U801-LINE2RP-Pad9)") (class "Default")
      (node (ref "U801") (pin "9") (pinfunction "LINE2RP_9") (pintype "passive+no_connect"))
    )
    (net (code "49") (name "unconnected-(U801-MIC3L-Pad11)") (class "Default")
      (node (ref "U801") (pin "11") (pinfunction "MIC3L_11") (pintype "passive+no_connect"))
    )
    (net (code "50") (name "unconnected-(U801-MONO_LOM-Pad28)") (class "Default")
      (node (ref "U801") (pin "28") (pinfunction "MONO_LOM_28") (pintype "passive+no_connect"))
    )
    (net (code "51") (name "unconnected-(U801-MONO_LOP-Pad27)") (class "Default")
      (node (ref "U801") (pin "27") (pinfunction "MONO_LOP_27") (pintype "passive+no_connect"))
    )
    (net (code "52") (name "unconnected-(U801-RIGHT_LOM-Pad32)") (class "Default")
      (node (ref "U801") (pin "32") (pinfunction "RIGHT_LOM_32") (pintype "passive+no_connect"))
    )
    (net (code "53") (name "unconnected-(U801-RIGHT_LOP-Pad31)") (class "Default")
      (node (ref "U801") (pin "31") (pinfunction "RIGHT_LOP_31") (pintype "passive+no_connect"))
    )
  )
)
